# Analog_Frontend02.net
KiCad netlist of a schematic drawn in Altium Designer
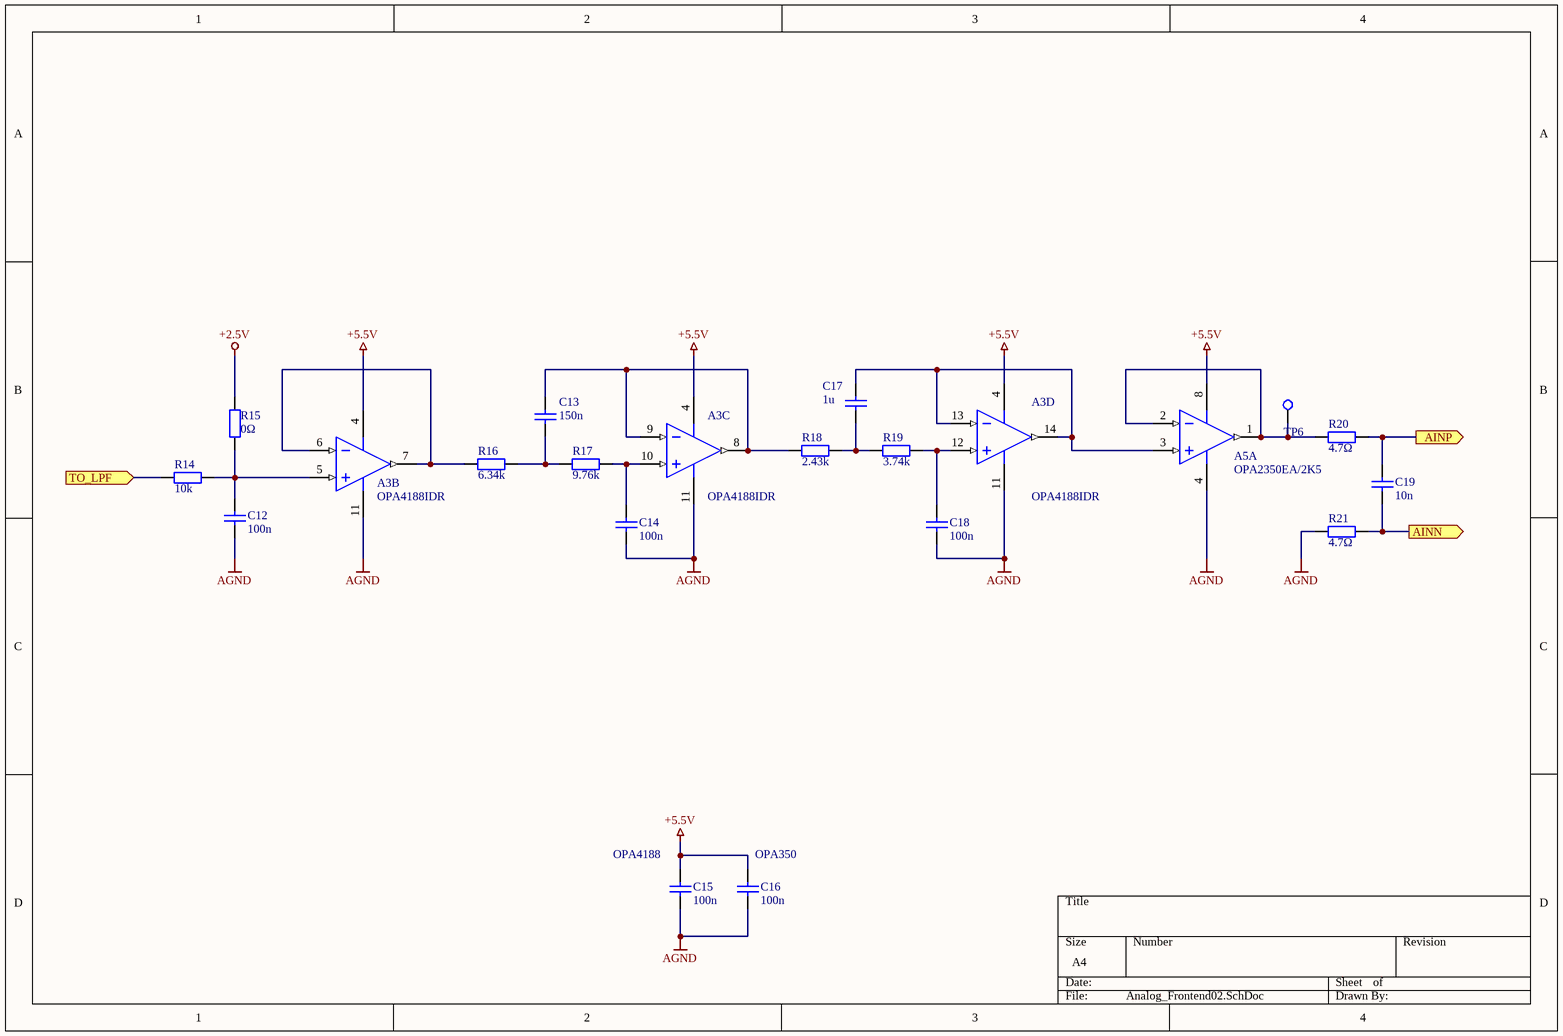
[diagram p0: Analog_Frontend02.SchDoc]

(export (version "E")
  (design (tool "Eeschema 10.0.6"))
  (components
    (comp (ref "A3")
      (value "OPA4188IDR")
      (footprint "SOIC127P600X175-14N")
      (libsource (lib "Analog Devices Operational Amplifiers") (part "AD824ARZ-14-3V-RL"))
    )
    (comp (ref "A5")
      (value "OPA2350EA/2K5")
      (footprint "SOIC127P600X175-8N")
      (libsource (lib "TI Amplifiers and Linear Operational Amplifier Precision Amplifier Part One") (part "OPA2350EA/250"))
    )
    (comp (ref "C12")
      (value "100n")
      (footprint "CAPC1608X87N")
      (libsource (lib "Miscellaneous Devices") (part "Cap"))
    )
    (comp (ref "C13")
      (value "150n")
      (footprint "CAPC1608X87N")
      (libsource (lib "Miscellaneous Devices") (part "Cap"))
    )
    (comp (ref "C14")
      (value "100n")
      (footprint "CAPC1608X87N")
      (libsource (lib "Miscellaneous Devices") (part "Cap"))
    )
    (comp (ref "C15")
      (value "100n")
      (footprint "CAPC1608X87N")
      (libsource (lib "Miscellaneous Devices") (part "Cap"))
    )
    (comp (ref "C16")
      (value "100n")
      (footprint "CAPC1608X87N")
      (libsource (lib "Miscellaneous Devices") (part "Cap"))
    )
    (comp (ref "C17")
      (value "1u")
      (footprint "CAPC1608X87N")
      (libsource (lib "Miscellaneous Devices") (part "Cap"))
    )
    (comp (ref "C18")
      (value "100n")
      (footprint "CAPC1608X87N")
      (libsource (lib "Miscellaneous Devices") (part "Cap"))
    )
    (comp (ref "C19")
      (value "10n")
      (footprint "CAPC1608X87N")
      (libsource (lib "Miscellaneous Devices") (part "Cap"))
    )
    (comp (ref "R14")
      (value "10k")
      (footprint "RESC1608X55N")
      (fields (field (name "MOUSER PART NUMBER") "603-RC0603FR-0710KL"))
      (libsource (lib "Miscellaneous Devices") (part "Res2"))
    )
    (comp (ref "R15") (value "0Ω") (footprint "RESC1608X55N") (libsource (lib "") (part "Res2_1")))
    (comp (ref "R16")
      (value "6.34k")
      (footprint "RESC1608X55N")
      (libsource (lib "Miscellaneous Devices") (part "Res2"))
    )
    (comp (ref "R17")
      (value "9.76k")
      (footprint "RESC1608X55N")
      (libsource (lib "Miscellaneous Devices") (part "Res2"))
    )
    (comp (ref "R18")
      (value "2.43k")
      (footprint "RESC1608X55N")
      (libsource (lib "Miscellaneous Devices") (part "Res2"))
    )
    (comp (ref "R19")
      (value "3.74k")
      (footprint "RESC1608X55N")
      (libsource (lib "Miscellaneous Devices") (part "Res2"))
    )
    (comp (ref "R20")
      (value "4.7Ω")
      (footprint "RESC1608X55N")
      (libsource (lib "Miscellaneous Devices") (part "Res2"))
    )
    (comp (ref "R21")
      (value "4.7Ω")
      (footprint "RESC1608X55N")
      (libsource (lib "Miscellaneous Devices") (part "Res2"))
    )
    (comp (ref "TP6")
      (value "TP")
      (footprint "TEST-POINT")
      (description "Generic test point")
      (libsource (lib "Custom_Lib") (part "TEST_POINT"))
    )
  )
  (nets
    (net (code "1") (name "+2.5V") (class "Default")
      (node (ref "R15") (pin "2") (pinfunction "2_2") (pintype "passive"))
    )
    (net (code "2") (name "+5.5V") (class "Default")
      (node (ref "A3") (pin "4") (pinfunction "+V_4") (pintype "power_in"))
      (node (ref "A5") (pin "8") (pinfunction "V+_8") (pintype "power_in"))
      (node (ref "C15") (pin "2") (pinfunction "2_2") (pintype "passive"))
      (node (ref "C16") (pin "2") (pinfunction "2_2") (pintype "passive"))
    )
    (net (code "3") (name "/AINN") (class "Default")
      (node (ref "C19") (pin "1") (pinfunction "1_1") (pintype "passive"))
      (node (ref "R21") (pin "2") (pinfunction "2_2") (pintype "passive"))
    )
    (net (code "4") (name "/AINP") (class "Default")
      (node (ref "C19") (pin "2") (pinfunction "2_2") (pintype "passive"))
      (node (ref "R20") (pin "2") (pinfunction "2_2") (pintype "passive"))
    )
    (net (code "5") (name "/TO_LPF") (class "Default")
      (node (ref "R14") (pin "1") (pinfunction "1_1") (pintype "passive"))
    )
    (net (code "6") (name "AGND") (class "Default")
      (node (ref "A3") (pin "11") (pinfunction "-V_11") (pintype "power_in"))
      (node (ref "A5") (pin "4") (pinfunction "V-_4") (pintype "power_in"))
      (node (ref "C12") (pin "1") (pinfunction "1_1") (pintype "passive"))
      (node (ref "C14") (pin "1") (pinfunction "1_1") (pintype "passive"))
      (node (ref "C15") (pin "1") (pinfunction "1_1") (pintype "passive"))
      (node (ref "C16") (pin "1") (pinfunction "1_1") (pintype "passive"))
      (node (ref "C18") (pin "1") (pinfunction "1_1") (pintype "passive"))
      (node (ref "R21") (pin "1") (pinfunction "1_1") (pintype "passive"))
    )
    (net (code "7") (name "Net-(A3B-+IN_B)") (class "Default")
      (node (ref "A3") (pin "5") (pinfunction "+IN_B_5") (pintype "input"))
      (node (ref "C12") (pin "2") (pinfunction "2_2") (pintype "passive"))
      (node (ref "R14") (pin "2") (pinfunction "2_2") (pintype "passive"))
      (node (ref "R15") (pin "1") (pinfunction "1_1") (pintype "passive"))
    )
    (net (code "8") (name "Net-(A3B--IN_B)") (class "Default")
      (node (ref "A3") (pin "6") (pinfunction "-IN_B_6") (pintype "input"))
      (node (ref "A3") (pin "7") (pinfunction "OUT_B_7") (pintype "output"))
      (node (ref "R16") (pin "1") (pinfunction "1_1") (pintype "passive"))
    )
    (net (code "9") (name "Net-(A3C-+IN_C)") (class "Default")
      (node (ref "A3") (pin "10") (pinfunction "+IN_C_10") (pintype "input"))
      (node (ref "C14") (pin "2") (pinfunction "2_2") (pintype "passive"))
      (node (ref "R17") (pin "2") (pinfunction "2_2") (pintype "passive"))
    )
    (net (code "10") (name "Net-(A3C--IN_C)") (class "Default")
      (node (ref "A3") (pin "8") (pinfunction "OUT_C_8") (pintype "output"))
      (node (ref "A3") (pin "9") (pinfunction "-IN_C_9") (pintype "input"))
      (node (ref "C13") (pin "2") (pinfunction "2_2") (pintype "passive"))
      (node (ref "R18") (pin "1") (pinfunction "1_1") (pintype "passive"))
    )
    (net (code "11") (name "Net-(A3D-+IN_D)") (class "Default")
      (node (ref "A3") (pin "12") (pinfunction "+IN_D_12") (pintype "input"))
      (node (ref "C18") (pin "2") (pinfunction "2_2") (pintype "passive"))
      (node (ref "R19") (pin "2") (pinfunction "2_2") (pintype "passive"))
    )
    (net (code "12") (name "Net-(A3D--IN_D)") (class "Default")
      (node (ref "A3") (pin "13") (pinfunction "-IN_D_13") (pintype "input"))
      (node (ref "A3") (pin "14") (pinfunction "OUT_D_14") (pintype "output"))
      (node (ref "A5") (pin "3") (pinfunction "IN_A+_3") (pintype "input"))
      (node (ref "C17") (pin "2") (pinfunction "2_2") (pintype "passive"))
    )
    (net (code "13") (name "Net-(A5A-IN_A-)") (class "Default")
      (node (ref "A5") (pin "1") (pinfunction "OUT_A_1") (pintype "output"))
      (node (ref "A5") (pin "2") (pinfunction "IN_A-_2") (pintype "input"))
      (node (ref "R20") (pin "1") (pinfunction "1_1") (pintype "passive"))
      (node (ref "TP6") (pin "0") (pinfunction "0_0") (pintype "passive"))
    )
    (net (code "14") (name "Net-(C13-Pad1)") (class "Default")
      (node (ref "C13") (pin "1") (pinfunction "1_1") (pintype "passive"))
      (node (ref "R16") (pin "2") (pinfunction "2_2") (pintype "passive"))
      (node (ref "R17") (pin "1") (pinfunction "1_1") (pintype "passive"))
    )
    (net (code "15") (name "Net-(C17-Pad1)") (class "Default")
      (node (ref "C17") (pin "1") (pinfunction "1_1") (pintype "passive"))
      (node (ref "R18") (pin "2") (pinfunction "2_2") (pintype "passive"))
      (node (ref "R19") (pin "1") (pinfunction "1_1") (pintype "passive"))
    )
  )
)
